# SH4_-_MICROCONTROLLER.net
KiCad netlist of a schematic drawn in Altium Designer
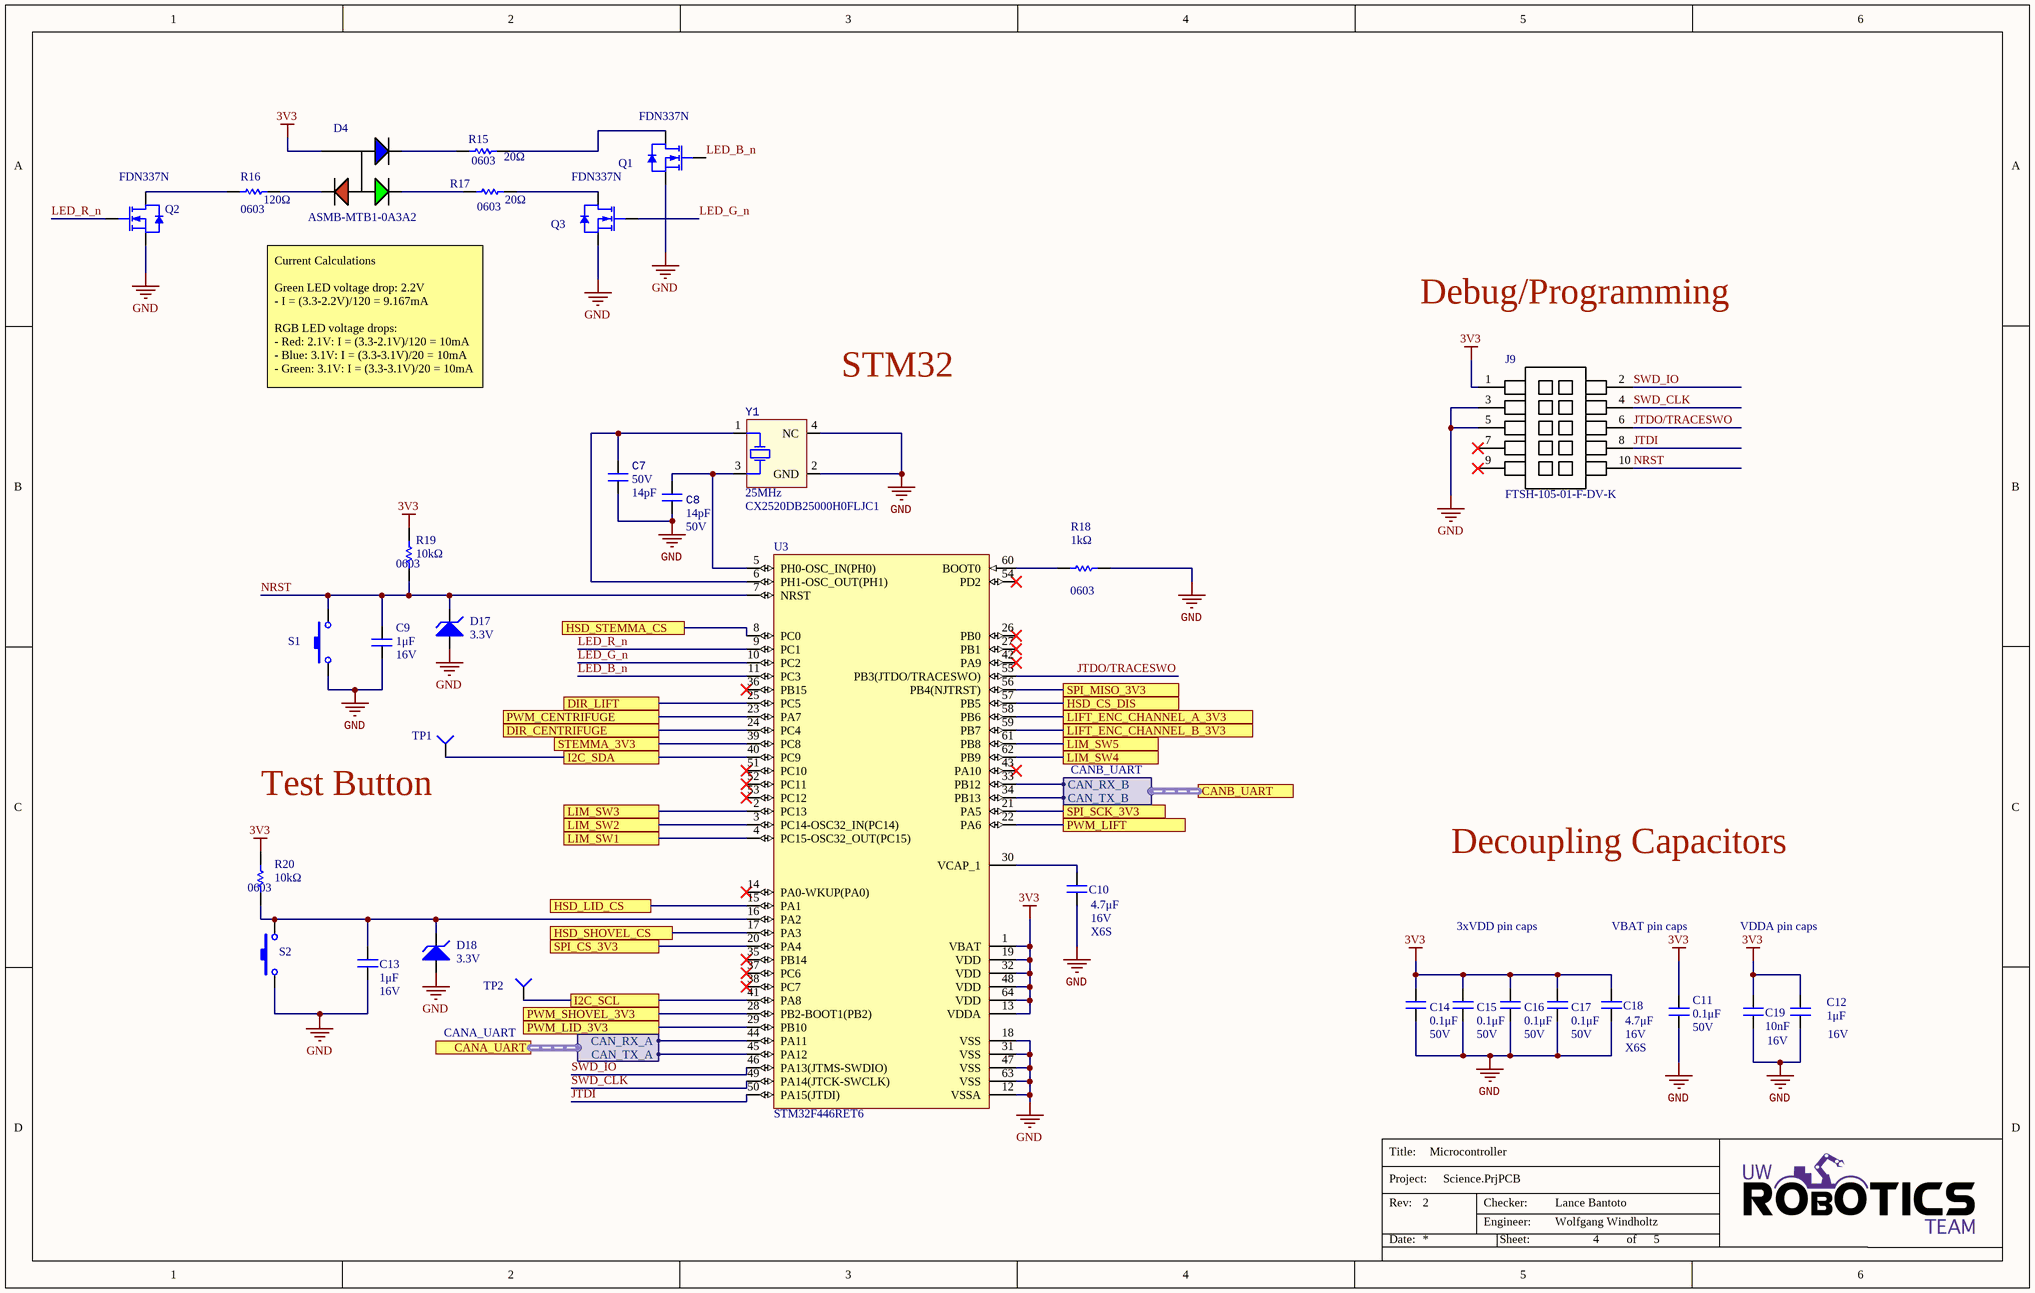
[diagram p0: SH4 - MICROCONTROLLER.SchDoc]

(export (version "E")
  (design (tool "Eeschema 10.0.6"))
  (components
    (comp (ref "C7")
      (value "14pF")
      (footprint "CAP0603")
      (description "CAP CER 14PF 50V C0G/NP0 0603")
      (fields (field (name "VOLTAGE RATING") "50V") (field (name "Comment") "CAP_14pF_50V_0603"))
      (libsource (lib "UWRT_Schematic_Library_2020") (part "CAP_14pF_50V_0603"))
    )
    (comp (ref "C8")
      (value "14pF")
      (footprint "CAP0603")
      (description "CAP CER 14PF 50V C0G/NP0 0603")
      (fields (field (name "VOLTAGE RATING") "50V") (field (name "Comment") "CAP_14pF_50V_0603"))
      (libsource (lib "UWRT_Schematic_Library_2020") (part "CAP_14pF_50V_0603"))
    )
    (comp (ref "C9")
      (value "1μF")
      (footprint "CAP0603")
      (description "CAP CER 1UF 16V Y5V 0603")
      (fields
        (field (name "VOLTAGE RATING") "16V")
        (field (name "MANUFACTURER PART NUMBER") "CC0603ZRY5V7BB105")
        (field (name "Comment") "CAP_1uF_16V_0603")
      )
      (libsource (lib "UWRT_Schematic_Library_2020") (part "CAP_1uF_16V_0603"))
    )
    (comp (ref "C10")
      (value "4.7μF")
      (footprint "CAP0603")
      (description "CAP CER 4.7UF 16V X6S 0603")
      (fields
        (field (name "DIELECTRIC") "X6S")
        (field (name "VOLTAGE RATING") "16V")
        (field (name "Comment") "CAP_4.7uF_16V_0603")
      )
      (libsource (lib "UWRT_Schematic_Library_2020") (part "CAP_4.7uF_16V_0603"))
    )
    (comp (ref "C11")
      (value "0.1μF")
      (footprint "CAP0603")
      (description "CAP CER 0.1UF 50V X7R 0603")
      (fields (field (name "VOLTAGE RATING") "50V") (field (name "Comment") "CAP_0.1uF_50V_0603"))
      (libsource (lib "UWRT_Schematic_Library_2020") (part "CAP_0.1uF_50V_0603"))
    )
    (comp (ref "C12")
      (value "1μF")
      (footprint "CAP0603")
      (description "CAP CER 1UF 16V Y5V 0603")
      (fields
        (field (name "VOLTAGE RATING") "16V")
        (field (name "MANUFACTURER PART NUMBER") "CC0603ZRY5V7BB105")
        (field (name "Comment") "CAP_1uF_16V_0603")
      )
      (libsource (lib "UWRT_Schematic_Library_2020") (part "CAP_1uF_16V_0603"))
    )
    (comp (ref "C13")
      (value "1μF")
      (footprint "CAP0603")
      (description "CAP CER 1UF 16V Y5V 0603")
      (fields
        (field (name "VOLTAGE RATING") "16V")
        (field (name "MANUFACTURER PART NUMBER") "CC0603ZRY5V7BB105")
        (field (name "Comment") "CAP_1uF_16V_0603")
      )
      (libsource (lib "UWRT_Schematic_Library_2020") (part "CAP_1uF_16V_0603"))
    )
    (comp (ref "C14")
      (value "0.1μF")
      (footprint "CAP0603")
      (description "CAP CER 0.1UF 50V X7R 0603")
      (fields (field (name "VOLTAGE RATING") "50V") (field (name "Comment") "CAP_0.1uF_50V_0603"))
      (libsource (lib "UWRT_Schematic_Library_2020") (part "CAP_0.1uF_50V_0603"))
    )
    (comp (ref "C15")
      (value "0.1μF")
      (footprint "CAP0603")
      (description "CAP CER 0.1UF 50V X7R 0603")
      (fields (field (name "VOLTAGE RATING") "50V") (field (name "Comment") "CAP_0.1uF_50V_0603"))
      (libsource (lib "UWRT_Schematic_Library_2020") (part "CAP_0.1uF_50V_0603"))
    )
    (comp (ref "C16")
      (value "0.1μF")
      (footprint "CAP0603")
      (description "CAP CER 0.1UF 50V X7R 0603")
      (fields (field (name "VOLTAGE RATING") "50V") (field (name "Comment") "CAP_0.1uF_50V_0603"))
      (libsource (lib "UWRT_Schematic_Library_2020") (part "CAP_0.1uF_50V_0603"))
    )
    (comp (ref "C17")
      (value "0.1μF")
      (footprint "CAP0603")
      (description "CAP CER 0.1UF 50V X7R 0603")
      (fields (field (name "VOLTAGE RATING") "50V") (field (name "Comment") "CAP_0.1uF_50V_0603"))
      (libsource (lib "UWRT_Schematic_Library_2020") (part "CAP_0.1uF_50V_0603"))
    )
    (comp (ref "C18")
      (value "4.7μF")
      (footprint "CAP0603")
      (description "CAP CER 4.7UF 16V X6S 0603")
      (fields
        (field (name "DIELECTRIC") "X6S")
        (field (name "VOLTAGE RATING") "16V")
        (field (name "Comment") "CAP_4.7uF_16V_0603")
      )
      (libsource (lib "UWRT_Schematic_Library_2020") (part "CAP_4.7uF_16V_0603"))
    )
    (comp (ref "C19")
      (value "10nF")
      (footprint "CAP0603")
      (description "CAP CER 10000PF 16V X7R 0603")
      (fields (field (name "VOLTAGE RATING") "16V") (field (name "Comment") "CAP_10nF_0603"))
      (libsource (lib "UWRT_Schematic_Library_2020") (part "CAP_10nF_0603"))
    )
    (comp (ref "D4")
      (value "LED_RGB")
      (footprint "LED_RGB")
      (description "LED RGB DIFFUSED 4PLCC SMD")
      (fields (field (name "MANUFACTURER PART NUMBER 1") "ASMB-MTB1-0A3A2"))
      (libsource (lib "UWRT_Schematic_Library_2020") (part "LED_RGB"))
    )
    (comp (ref "D17")
      (value "ESD5Z3.3T1G")
      (footprint "SOD523_UNI")
      (description "TVS DIODE 3.3V 14.1V SOD523")
      (fields (field (name "REVERSE STANDOFF VOLTAGE") "3.3V"))
      (libsource (lib "UWRT_Schematic_Library_2020") (part "ESD5Z3.3T1G"))
    )
    (comp (ref "D18")
      (value "ESD5Z3.3T1G")
      (footprint "SOD523_UNI")
      (description "TVS DIODE 3.3V 14.1V SOD523")
      (fields (field (name "REVERSE STANDOFF VOLTAGE") "3.3V"))
      (libsource (lib "UWRT_Schematic_Library_2020") (part "ESD5Z3.3T1G"))
    )
    (comp (ref "J9")
      (value "CON_PROGRAMMING")
      (footprint "FTSH-105-01-F-DV-K-P-TR")
      (description "CONN HEADER SMD 10POS 1.27MM")
      (fields (field (name "MANUFACTURER PART NUMBER 1") "FTSH-105-01-F-DV-K"))
      (libsource (lib "UWRT_Schematic_Library_2020") (part "CON_PROGRAMMING"))
    )
    (comp (ref "Q1")
      (value "NMOS_30V_2.2A")
      (footprint "NMOS_SSOT-3")
      (description "MOSFET N-CH 30V 2.2A SUPERSOT3")
      (fields (field (name "MANUFACTURER PART NUMBER 1") "FDN337N"))
      (libsource (lib "UWRT_Schematic_Library_2020") (part "NMOS_30V_2.2A"))
    )
    (comp (ref "Q2")
      (value "NMOS_30V_2.2A")
      (footprint "NMOS_SSOT-3")
      (description "MOSFET N-CH 30V 2.2A SUPERSOT3")
      (fields (field (name "MANUFACTURER PART NUMBER 1") "FDN337N"))
      (libsource (lib "UWRT_Schematic_Library_2020") (part "NMOS_30V_2.2A"))
    )
    (comp (ref "Q3")
      (value "NMOS_30V_2.2A")
      (footprint "NMOS_SSOT-3")
      (description "MOSFET N-CH 30V 2.2A SUPERSOT3")
      (fields (field (name "MANUFACTURER PART NUMBER 1") "FDN337N"))
      (libsource (lib "UWRT_Schematic_Library_2020") (part "NMOS_30V_2.2A"))
    )
    (comp (ref "R15")
      (value "20Ω")
      (footprint "RESC0603")
      (description "RES 20 OHM 5% 1/10W 0603")
      (fields
        (field (name "TOLERANCE") "5%")
        (field (name "PACKAGE/FOOTPRINT") "0603")
        (field (name "Comment") "RES_20Ω_0603_5%")
      )
      (libsource (lib "UWRT_Schematic_Library_2020") (part "RES_20Ω_0603_5%"))
    )
    (comp (ref "R16")
      (value "120Ω")
      (footprint "RESC0603")
      (description "RES 120 OHM 5% 1/10W 0603")
      (fields (field (name "PACKAGE/FOOTPRINT") "0603") (field (name "Comment") "RES_120Ω_0603"))
      (libsource (lib "UWRT_Schematic_Library_2020") (part "RES_120Ω_0603_5%"))
    )
    (comp (ref "R17")
      (value "20Ω")
      (footprint "RESC0603")
      (description "RES 20 OHM 5% 1/10W 0603")
      (fields
        (field (name "TOLERANCE") "5%")
        (field (name "PACKAGE/FOOTPRINT") "0603")
        (field (name "Comment") "RES_20Ω_0603_5%")
      )
      (libsource (lib "UWRT_Schematic_Library_2020") (part "RES_20Ω_0603_5%"))
    )
    (comp (ref "R18")
      (value "1kΩ")
      (footprint "RESC0603")
      (description "RES 1K OHM 5% 1/10W 0603")
      (fields
        (field (name "TOLERANCE") "5%")
        (field (name "PACKAGE/FOOTPRINT") "0603")
        (field (name "Comment") "RES_1kΩ_0603_5%")
      )
      (libsource (lib "UWRT_Schematic_Library_2020") (part "RES_1kΩ_0603_5%"))
    )
    (comp (ref "R19")
      (value "10kΩ")
      (footprint "RESC0603")
      (description "RES 10K OHM 5% 1/10W 0603")
      (fields
        (field (name "TOLERANCE") "5%")
        (field (name "PACKAGE/FOOTPRINT") "0603")
        (field (name "Comment") "RES_10kΩ_0603_5%")
      )
      (libsource (lib "UWRT_Schematic_Library_2020") (part "RES_10kΩ_0603_5%"))
    )
    (comp (ref "R20")
      (value "10kΩ")
      (footprint "RESC0603")
      (description "RES 10K OHM 5% 1/10W 0603")
      (fields
        (field (name "TOLERANCE") "5%")
        (field (name "PACKAGE/FOOTPRINT") "0603")
        (field (name "Comment") "RES_10kΩ_0603_5%")
      )
      (libsource (lib "UWRT_Schematic_Library_2020") (part "RES_10kΩ_0603_5%"))
    )
    (comp (ref "S1")
      (value "SW_TACTILE")
      (footprint "B3U-1000P")
      (description "SWITCH TACTILE SPST-NO 0.05A 12V")
      (libsource (lib "UWRT_Schematic_Library_2020") (part "SW_TACTILE"))
    )
    (comp (ref "S2")
      (value "SW_TACTILE")
      (footprint "B3U-1000P")
      (description "SWITCH TACTILE SPST-NO 0.05A 12V")
      (libsource (lib "UWRT_Schematic_Library_2020") (part "SW_TACTILE"))
    )
    (comp (ref "TP1")
      (value "TESTPOINT_1MM_CIRCLE")
      (footprint "TESTPOINT_CIRCLE_1MM")
      (description "TESTPOINT 1MM CIRCLE")
      (libsource (lib "UWRT_Schematic_Library_2020") (part "TESTPOINT_1MM_CIRCLE"))
    )
    (comp (ref "TP2")
      (value "TESTPOINT_1MM_CIRCLE")
      (footprint "TESTPOINT_CIRCLE_1MM")
      (description "TESTPOINT 1MM CIRCLE")
      (libsource (lib "UWRT_Schematic_Library_2020") (part "TESTPOINT_1MM_CIRCLE"))
    )
    (comp (ref "U3")
      (value "STM32F446RET6")
      (footprint "STM-LQFP64_L")
      (libsource (lib "UWRT_Schematic_Library_2020") (part "MCU_STM32F446RET6"))
    )
    (comp (ref "Y1")
      (value "CRYSTAL_25MHZ")
      (footprint "SOIC254P1016X440-4N")
      (description "CRYSTAL 25.0000MHZ 12PF SMD")
      (fields
        (field (name "FREQUENCY") "25MHz")
        (field (name "MANUFACTURER PART NUMBER 1") "CX2520DB25000H0FLJC1")
      )
      (libsource (lib "UWRT_Schematic_Library_2020") (part "CRYSTAL_25MHZ"))
    )
  )
  (nets
    (net (code "3") (name "/CAN_RX_A") (class "Default")
      (node (ref "U3") (pin "44") (pinfunction "PA11_44") (pintype "bidirectional"))
    )
    (net (code "4") (name "/CAN_RX_B") (class "Default")
      (node (ref "U3") (pin "33") (pinfunction "PB12_33") (pintype "bidirectional"))
    )
    (net (code "5") (name "/CAN_TX_A") (class "Default")
      (node (ref "U3") (pin "45") (pinfunction "PA12_45") (pintype "bidirectional"))
    )
    (net (code "6") (name "/CAN_TX_B") (class "Default")
      (node (ref "U3") (pin "34") (pinfunction "PB13_34") (pintype "bidirectional"))
    )
    (net (code "7") (name "/DIR_CENTRIFUGE") (class "Default")
      (node (ref "U3") (pin "24") (pinfunction "PC4_24") (pintype "bidirectional"))
    )
    (net (code "8") (name "/DIR_LIFT") (class "Default")
      (node (ref "U3") (pin "25") (pinfunction "PC5_25") (pintype "bidirectional"))
    )
    (net (code "9") (name "/HSD_CS_DIS") (class "Default")
      (node (ref "U3") (pin "57") (pinfunction "PB5_57") (pintype "bidirectional"))
    )
    (net (code "10") (name "/HSD_LID_CS") (class "Default")
      (node (ref "U3") (pin "15") (pinfunction "PA1_15") (pintype "bidirectional"))
    )
    (net (code "11") (name "/HSD_SHOVEL_CS") (class "Default")
      (node (ref "U3") (pin "17") (pinfunction "PA3_17") (pintype "bidirectional"))
    )
    (net (code "12") (name "/HSD_STEMMA_CS") (class "Default")
      (node (ref "U3") (pin "8") (pinfunction "PC0_8") (pintype "bidirectional"))
    )
    (net (code "13") (name "/I2C_SCL") (class "Default")
      (node (ref "TP2") (pin "1") (pinfunction "=value_1") (pintype "passive"))
      (node (ref "U3") (pin "41") (pinfunction "PA8_41") (pintype "bidirectional"))
    )
    (net (code "14") (name "/I2C_SDA") (class "Default")
      (node (ref "TP1") (pin "1") (pinfunction "=value_1") (pintype "passive"))
      (node (ref "U3") (pin "40") (pinfunction "PC9_40") (pintype "bidirectional"))
    )
    (net (code "15") (name "/JTDI") (class "Default")
      (node (ref "J9") (pin "8") (pinfunction "8_8") (pintype "passive"))
      (node (ref "U3") (pin "50") (pinfunction "PA15(JTDI)_50") (pintype "bidirectional"))
    )
    (net (code "16") (name "/JTDO{slash}TRACESWO") (class "Default")
      (node (ref "J9") (pin "6") (pinfunction "6_6") (pintype "passive"))
      (node (ref "U3") (pin "55") (pinfunction "PB3(JTDO/TRACESWO)_55") (pintype "bidirectional"))
    )
    (net (code "17") (name "/LED_B_n") (class "Default")
      (node (ref "Q1") (pin "1") (pinfunction "GATE_1") (pintype "passive"))
      (node (ref "U3") (pin "11") (pinfunction "PC3_11") (pintype "bidirectional"))
    )
    (net (code "18") (name "/LED_G_n") (class "Default")
      (node (ref "Q3") (pin "1") (pinfunction "GATE_1") (pintype "passive"))
      (node (ref "U3") (pin "10") (pinfunction "PC2_10") (pintype "bidirectional"))
    )
    (net (code "19") (name "/LED_R_n") (class "Default")
      (node (ref "Q2") (pin "1") (pinfunction "GATE_1") (pintype "passive"))
      (node (ref "U3") (pin "9") (pinfunction "PC1_9") (pintype "bidirectional"))
    )
    (net (code "20") (name "/LIFT_ENC_CHANNEL_A_3V3") (class "Default")
      (node (ref "U3") (pin "58") (pinfunction "PB6_58") (pintype "bidirectional"))
    )
    (net (code "21") (name "/LIFT_ENC_CHANNEL_B_3V3") (class "Default")
      (node (ref "U3") (pin "59") (pinfunction "PB7_59") (pintype "bidirectional"))
    )
    (net (code "22") (name "/LIM_SW1") (class "Default")
      (node (ref "U3") (pin "4") (pinfunction "PC15-OSC32_OUT(PC15)_4") (pintype "bidirectional"))
    )
    (net (code "23") (name "/LIM_SW2") (class "Default")
      (node (ref "U3") (pin "3") (pinfunction "PC14-OSC32_IN(PC14)_3") (pintype "bidirectional"))
    )
    (net (code "24") (name "/LIM_SW3") (class "Default")
      (node (ref "U3") (pin "2") (pinfunction "PC13_2") (pintype "bidirectional"))
    )
    (net (code "25") (name "/LIM_SW4") (class "Default")
      (node (ref "U3") (pin "62") (pinfunction "PB9_62") (pintype "bidirectional"))
    )
    (net (code "26") (name "/LIM_SW5") (class "Default")
      (node (ref "U3") (pin "61") (pinfunction "PB8_61") (pintype "bidirectional"))
    )
    (net (code "27") (name "/NRST") (class "Default")
      (node (ref "C9") (pin "2") (pinfunction "2_2") (pintype "passive"))
      (node (ref "D17") (pin "2") (pinfunction "Cathode_2") (pintype "passive"))
      (node (ref "J9") (pin "10") (pinfunction "10_10") (pintype "passive"))
      (node (ref "R19") (pin "1") (pinfunction "1_1") (pintype "passive"))
      (node (ref "S1") (pin "1") (pinfunction "1_1") (pintype "passive"))
      (node (ref "U3") (pin "7") (pinfunction "NRST_7") (pintype "bidirectional"))
    )
    (net (code "28") (name "/PWM_CENTRIFUGE") (class "Default")
      (node (ref "U3") (pin "23") (pinfunction "PA7_23") (pintype "bidirectional"))
    )
    (net (code "29") (name "/PWM_LID_3V3") (class "Default")
      (node (ref "U3") (pin "29") (pinfunction "PB10_29") (pintype "bidirectional"))
    )
    (net (code "30") (name "/PWM_LIFT") (class "Default")
      (node (ref "U3") (pin "22") (pinfunction "PA6_22") (pintype "bidirectional"))
    )
    (net (code "31") (name "/PWM_SHOVEL_3V3") (class "Default")
      (node (ref "U3") (pin "28") (pinfunction "PB2-BOOT1(PB2)_28") (pintype "bidirectional"))
    )
    (net (code "32") (name "/SPI_CS_3V3") (class "Default")
      (node (ref "U3") (pin "20") (pinfunction "PA4_20") (pintype "bidirectional"))
    )
    (net (code "33") (name "/SPI_MISO_3V3") (class "Default")
      (node (ref "U3") (pin "56") (pinfunction "PB4(NJTRST)_56") (pintype "bidirectional"))
    )
    (net (code "34") (name "/SPI_SCK_3V3") (class "Default")
      (node (ref "U3") (pin "21") (pinfunction "PA5_21") (pintype "bidirectional"))
    )
    (net (code "35") (name "/STEMMA_3V3") (class "Default")
      (node (ref "U3") (pin "39") (pinfunction "PC8_39") (pintype "bidirectional"))
    )
    (net (code "36") (name "/SWD_CLK") (class "Default")
      (node (ref "J9") (pin "4") (pinfunction "4_4") (pintype "passive"))
      (node (ref "U3") (pin "49") (pinfunction "PA14(JTCK-SWCLK)_49") (pintype "bidirectional"))
    )
    (net (code "37") (name "/SWD_IO") (class "Default")
      (node (ref "J9") (pin "2") (pinfunction "2_2") (pintype "passive"))
      (node (ref "U3") (pin "46") (pinfunction "PA13(JTMS-SWDIO)_46") (pintype "bidirectional"))
    )
    (net (code "40") (name "3V3") (class "Default")
      (node (ref "C11") (pin "2") (pinfunction "2_2") (pintype "passive"))
      (node (ref "C12") (pin "2") (pinfunction "2_2") (pintype "passive"))
      (node (ref "C14") (pin "2") (pinfunction "2_2") (pintype "passive"))
      (node (ref "C15") (pin "2") (pinfunction "2_2") (pintype "passive"))
      (node (ref "C16") (pin "2") (pinfunction "2_2") (pintype "passive"))
      (node (ref "C17") (pin "2") (pinfunction "2_2") (pintype "passive"))
      (node (ref "C18") (pin "2") (pinfunction "2_2") (pintype "passive"))
      (node (ref "C19") (pin "2") (pinfunction "2_2") (pintype "passive"))
      (node (ref "D4") (pin "4") (pinfunction "COMMON_ANODE_4") (pintype "passive"))
      (node (ref "J9") (pin "1") (pinfunction "1_1") (pintype "passive"))
      (node (ref "R19") (pin "2") (pinfunction "2_2") (pintype "passive"))
      (node (ref "R20") (pin "2") (pinfunction "2_2") (pintype "passive"))
      (node (ref "U3") (pin "1") (pinfunction "VBAT_1") (pintype "power_in"))
      (node (ref "U3") (pin "13") (pinfunction "VDDA_13") (pintype "power_in"))
      (node (ref "U3") (pin "19") (pinfunction "VDD_19") (pintype "power_in"))
      (node (ref "U3") (pin "32") (pinfunction "VDD_32") (pintype "power_in"))
      (node (ref "U3") (pin "48") (pinfunction "VDD_48") (pintype "power_in"))
      (node (ref "U3") (pin "64") (pinfunction "VDD_64") (pintype "power_in"))
    )
    (net (code "41") (name "GND") (class "Default")
      (node (ref "C10") (pin "1") (pinfunction "1_1") (pintype "passive"))
      (node (ref "C11") (pin "1") (pinfunction "1_1") (pintype "passive"))
      (node (ref "C12") (pin "1") (pinfunction "1_1") (pintype "passive"))
      (node (ref "C13") (pin "1") (pinfunction "1_1") (pintype "passive"))
      (node (ref "C14") (pin "1") (pinfunction "1_1") (pintype "passive"))
      (node (ref "C15") (pin "1") (pinfunction "1_1") (pintype "passive"))
      (node (ref "C16") (pin "1") (pinfunction "1_1") (pintype "passive"))
      (node (ref "C17") (pin "1") (pinfunction "1_1") (pintype "passive"))
      (node (ref "C18") (pin "1") (pinfunction "1_1") (pintype "passive"))
      (node (ref "C19") (pin "1") (pinfunction "1_1") (pintype "passive"))
      (node (ref "C7") (pin "1") (pinfunction "1_1") (pintype "passive"))
      (node (ref "C8") (pin "1") (pinfunction "1_1") (pintype "passive"))
      (node (ref "C9") (pin "1") (pinfunction "1_1") (pintype "passive"))
      (node (ref "D17") (pin "1") (pinfunction "Anode_1") (pintype "passive"))
      (node (ref "D18") (pin "1") (pinfunction "Anode_1") (pintype "passive"))
      (node (ref "J9") (pin "3") (pinfunction "3_3") (pintype "passive"))
      (node (ref "J9") (pin "5") (pinfunction "5_5") (pintype "passive"))
      (node (ref "Q1") (pin "2") (pinfunction "SOURCE_2") (pintype "passive"))
      (node (ref "Q2") (pin "2") (pinfunction "SOURCE_2") (pintype "passive"))
      (node (ref "Q3") (pin "2") (pinfunction "SOURCE_2") (pintype "passive"))
      (node (ref "R18") (pin "2") (pinfunction "2_2") (pintype "passive"))
      (node (ref "S1") (pin "2") (pinfunction "2_2") (pintype "passive"))
      (node (ref "S2") (pin "1") (pinfunction "1_1") (pintype "passive"))
      (node (ref "U3") (pin "12") (pinfunction "VSSA_12") (pintype "power_in"))
      (node (ref "U3") (pin "18") (pinfunction "VSS_18") (pintype "power_in"))
      (node (ref "U3") (pin "31") (pinfunction "VSS_31") (pintype "power_in"))
      (node (ref "U3") (pin "47") (pinfunction "VSS_47") (pintype "power_in"))
      (node (ref "U3") (pin "63") (pinfunction "VSS_63") (pintype "power_in"))
      (node (ref "Y1") (pin "2") (pinfunction "GND_2") (pintype "power_in"))
      (node (ref "Y1") (pin "4") (pinfunction "NC_4") (pintype "passive"))
    )
    (net (code "42") (name "Net-(D4-CATHODE_(BLUE))") (class "Default")
      (node (ref "D4") (pin "3") (pinfunction "CATHODE_(BLUE)_3") (pintype "passive"))
      (node (ref "R15") (pin "1") (pinfunction "1_1") (pintype "passive"))
    )
    (net (code "43") (name "Net-(D4-CATHODE_(GREEN))") (class "Default")
      (node (ref "D4") (pin "2") (pinfunction "CATHODE_(GREEN)_2") (pintype "passive"))
      (node (ref "R17") (pin "1") (pinfunction "1_1") (pintype "passive"))
    )
    (net (code "44") (name "Net-(D4-CATHODE_(RED))") (class "Default")
      (node (ref "D4") (pin "1") (pinfunction "CATHODE_(RED)_1") (pintype "passive"))
      (node (ref "R16") (pin "2") (pinfunction "2_2") (pintype "passive"))
    )
    (net (code "45") (name "Net-(D18-Cathode)") (class "Default")
      (node (ref "C13") (pin "2") (pinfunction "2_2") (pintype "passive"))
      (node (ref "D18") (pin "2") (pinfunction "Cathode_2") (pintype "passive"))
      (node (ref "R20") (pin "1") (pinfunction "1_1") (pintype "passive"))
      (node (ref "S2") (pin "2") (pinfunction "2_2") (pintype "passive"))
      (node (ref "U3") (pin "16") (pinfunction "PA2_16") (pintype "bidirectional"))
    )
    (net (code "46") (name "Net-(Q1-DRAIN)") (class "Default")
      (node (ref "Q1") (pin "3") (pinfunction "DRAIN_3") (pintype "passive"))
      (node (ref "R15") (pin "2") (pinfunction "2_2") (pintype "passive"))
    )
    (net (code "47") (name "Net-(Q2-DRAIN)") (class "Default")
      (node (ref "Q2") (pin "3") (pinfunction "DRAIN_3") (pintype "passive"))
      (node (ref "R16") (pin "1") (pinfunction "1_1") (pintype "passive"))
    )
    (net (code "48") (name "Net-(Q3-DRAIN)") (class "Default")
      (node (ref "Q3") (pin "3") (pinfunction "DRAIN_3") (pintype "passive"))
      (node (ref "R17") (pin "2") (pinfunction "2_2") (pintype "passive"))
    )
    (net (code "49") (name "Net-(U3-BOOT0)") (class "Default")
      (node (ref "R18") (pin "1") (pinfunction "1_1") (pintype "passive"))
      (node (ref "U3") (pin "60") (pinfunction "BOOT0_60") (pintype "input"))
    )
    (net (code "50") (name "Net-(U3-PH0-OSC_IN(PH0))") (class "Default")
      (node (ref "C8") (pin "2") (pinfunction "2_2") (pintype "passive"))
      (node (ref "U3") (pin "5") (pinfunction "PH0-OSC_IN(PH0)_5") (pintype "bidirectional"))
      (node (ref "Y1") (pin "3") (pinfunction "HOT_3") (pintype "passive"))
    )
    (net (code "51") (name "Net-(U3-PH1-OSC_OUT(PH1))") (class "Default")
      (node (ref "C7") (pin "2") (pinfunction "2_2") (pintype "passive"))
      (node (ref "U3") (pin "6") (pinfunction "PH1-OSC_OUT(PH1)_6") (pintype "bidirectional"))
      (node (ref "Y1") (pin "1") (pinfunction "HOT_1") (pintype "passive"))
    )
    (net (code "52") (name "Net-(U3-VCAP_1)") (class "Default")
      (node (ref "C10") (pin "2") (pinfunction "2_2") (pintype "passive"))
      (node (ref "U3") (pin "30") (pinfunction "VCAP_1_30") (pintype "passive"))
    )
    (net (code "53") (name "unconnected-(J9-Pad7)") (class "Default")
      (node (ref "J9") (pin "7") (pinfunction "7_7") (pintype "passive+no_connect"))
    )
    (net (code "54") (name "unconnected-(J9-Pad9)") (class "Default")
      (node (ref "J9") (pin "9") (pinfunction "9_9") (pintype "passive+no_connect"))
    )
    (net (code "55") (name "unconnected-(U3-PA0-WKUP(PA0)-Pad14)") (class "Default")
      (node (ref "U3") (pin "14") (pinfunction "PA0-WKUP(PA0)_14") (pintype "bidirectional+no_connect"))
    )
    (net (code "56") (name "unconnected-(U3-PA9-Pad42)") (class "Default")
      (node (ref "U3") (pin "42") (pinfunction "PA9_42") (pintype "bidirectional+no_connect"))
    )
    (net (code "57") (name "unconnected-(U3-PA10-Pad43)") (class "Default")
      (node (ref "U3") (pin "43") (pinfunction "PA10_43") (pintype "bidirectional+no_connect"))
    )
    (net (code "58") (name "unconnected-(U3-PB0-Pad26)") (class "Default")
      (node (ref "U3") (pin "26") (pinfunction "PB0_26") (pintype "bidirectional+no_connect"))
    )
    (net (code "59") (name "unconnected-(U3-PB1-Pad27)") (class "Default")
      (node (ref "U3") (pin "27") (pinfunction "PB1_27") (pintype "bidirectional+no_connect"))
    )
    (net (code "60") (name "unconnected-(U3-PB14-Pad35)") (class "Default")
      (node (ref "U3") (pin "35") (pinfunction "PB14_35") (pintype "bidirectional+no_connect"))
    )
    (net (code "61") (name "unconnected-(U3-PB15-Pad36)") (class "Default")
      (node (ref "U3") (pin "36") (pinfunction "PB15_36") (pintype "bidirectional+no_connect"))
    )
    (net (code "62") (name "unconnected-(U3-PC6-Pad37)") (class "Default")
      (node (ref "U3") (pin "37") (pinfunction "PC6_37") (pintype "bidirectional+no_connect"))
    )
    (net (code "63") (name "unconnected-(U3-PC7-Pad38)") (class "Default")
      (node (ref "U3") (pin "38") (pinfunction "PC7_38") (pintype "bidirectional+no_connect"))
    )
    (net (code "64") (name "unconnected-(U3-PC10-Pad51)") (class "Default")
      (node (ref "U3") (pin "51") (pinfunction "PC10_51") (pintype "bidirectional+no_connect"))
    )
    (net (code "65") (name "unconnected-(U3-PC11-Pad52)") (class "Default")
      (node (ref "U3") (pin "52") (pinfunction "PC11_52") (pintype "bidirectional+no_connect"))
    )
    (net (code "66") (name "unconnected-(U3-PC12-Pad53)") (class "Default")
      (node (ref "U3") (pin "53") (pinfunction "PC12_53") (pintype "bidirectional+no_connect"))
    )
    (net (code "67") (name "unconnected-(U3-PD2-Pad54)") (class "Default")
      (node (ref "U3") (pin "54") (pinfunction "PD2_54") (pintype "bidirectional+no_connect"))
    )
  )
)
